# POWER.net
KiCad netlist of a schematic drawn in Altium Designer
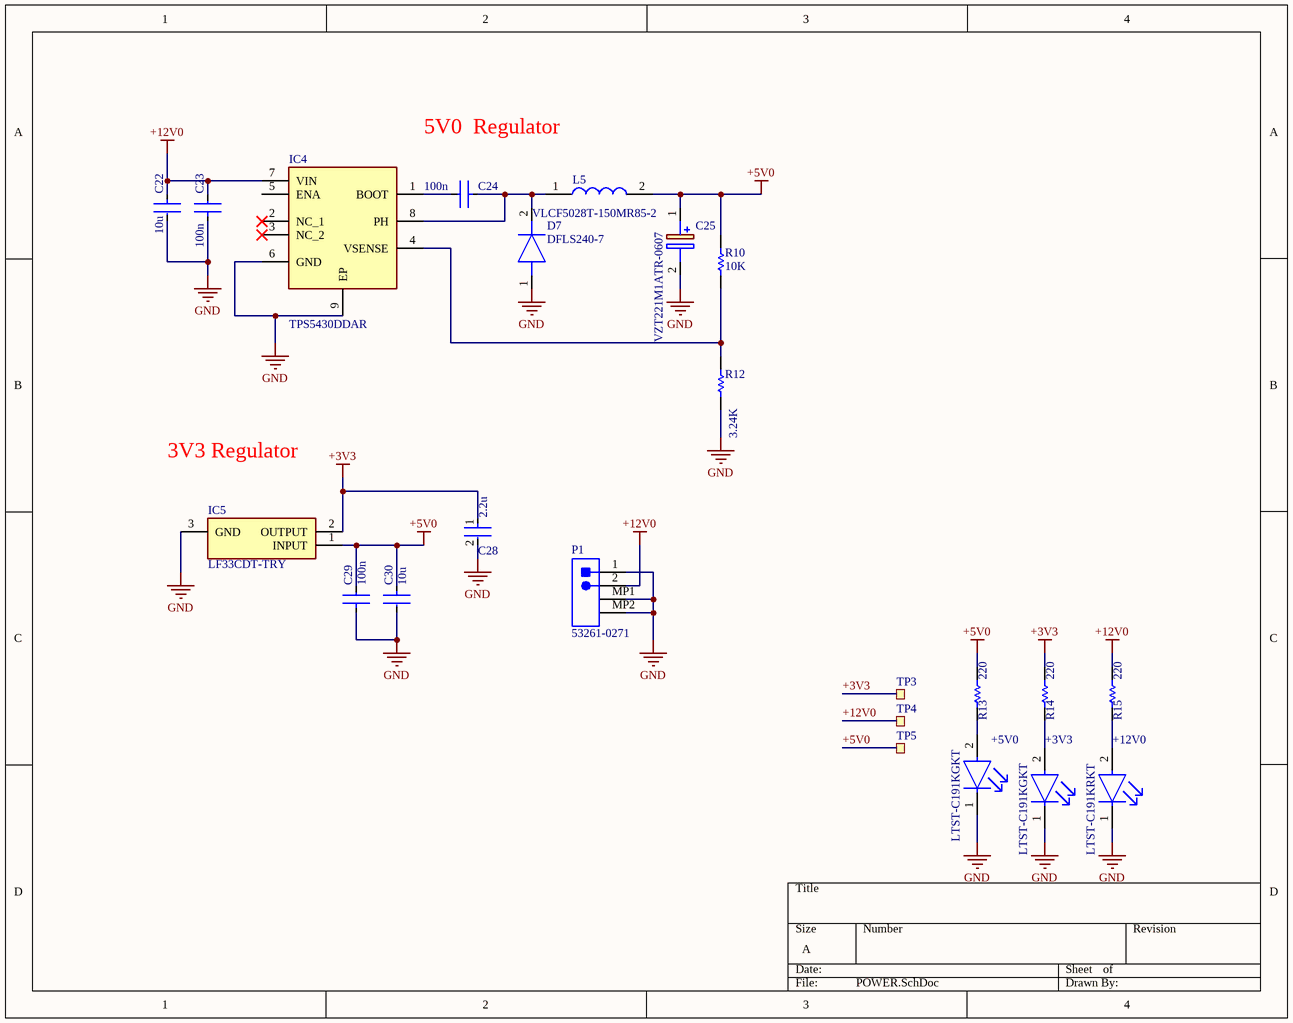
[diagram p0: POWER.SchDoc]

(export (version "E")
  (design (tool "Eeschema 10.0.6"))
  (components
    (comp (ref "+3V3")
      (value "LTST-C191KGKT")
      (footprint "FP-LTST-C191KGKT-MFG")
      (libsource (lib "Altium Content Vault") (part "8706943c75ba83719d021d2fdc84c58"))
    )
    (comp (ref "+5V0")
      (value "LTST-C191KGKT")
      (footprint "FP-LTST-C191KGKT-MFG")
      (libsource (lib "Altium Content Vault") (part "8706943c75ba83719d021d2fdc84c58"))
    )
    (comp (ref "+12V0")
      (value "LTST-C191KRKT")
      (footprint "FP-LTST-C191KRKT-MFG")
      (fields (field (name "VOLTAGE") "2V"))
      (libsource (lib "Altium Content Vault") (part "8706943c75ba83719d021d2fdc84c58"))
    )
    (comp (ref "C22")
      (value "10u")
      (footprint "FP-C1608-080-IPC_A")
      (description "CAP CER 10UF 25V X5R 0603")
      (fields (field (name "TOLERANCE") "20%") (field (name "Comment") "C1608X5R1E106M080AC"))
      (libsource (lib "") (part "11868f565c42a9108669ba33697ecf6_1"))
    )
    (comp (ref "C23")
      (value "100n")
      (footprint "FP-C1005-050-0_05-IPC_C")
      (description "Multilayer Ceramic Capacitors 100nF ±10% 50V X7R SMD 0402")
      (fields (field (name "VOLTAGE") "50V") (field (name "TOLERANCE") "10%"))
      (libsource (lib "Altium Content Vault") (part "b4654b650e69147ec39a6b967a45e02"))
    )
    (comp (ref "C24")
      (value "100n")
      (footprint "FP-C1005-050-0_05-IPC_C")
      (description "Multilayer Ceramic Capacitors 100nF ±10% 50V X7R SMD 0402")
      (fields (field (name "VOLTAGE") "50V") (field (name "TOLERANCE") "10%"))
      (libsource (lib "Altium Content Vault") (part "b4654b650e69147ec39a6b967a45e02"))
    )
    (comp (ref "C25")
      (value "VZT221M1ATR-0607")
      (footprint "SamacSys:CAPAE660X800N")
      (description "Capacitor Polarised")
      (fields (field (name "MOUSER PART NUMBER") "140-VZT221M1ATR-0607"))
      (libsource (lib "*") (part "VZT221M1ATR-0607"))
    )
    (comp (ref "C28")
      (value "C1005X5R1V225K050BC")
      (footprint "FP-C1005-050-0_15-IPC_A")
      (description "CAP CER 2.2UF 35V X5R 0402")
      (fields (field (name "CAPACITANCE") "2.2u") (field (name "TOLERANCE") "10%"))
      (libsource (lib "Altium Content Vault") (part "11868f565c42a9108669ba33697ecf6"))
    )
    (comp (ref "C29")
      (value "100n")
      (footprint "FP-C1005-050-0_05-IPC_C")
      (description "Multilayer Ceramic Capacitors 100nF ±10% 50V X7R SMD 0402")
      (fields (field (name "VOLTAGE") "50V") (field (name "TOLERANCE") "10%"))
      (libsource (lib "Altium Content Vault") (part "b4654b650e69147ec39a6b967a45e02"))
    )
    (comp (ref "C30")
      (value "10u")
      (footprint "FP-C1608-080-IPC_A")
      (description "CAP CER 10UF 25V X5R 0603")
      (fields (field (name "TOLERANCE") "20%") (field (name "Comment") "C1608X5R1E106M080AC"))
      (libsource (lib "") (part "11868f565c42a9108669ba33697ecf6_1"))
    )
    (comp (ref "D7")
      (value "DFLS240-7")
      (footprint "SamacSys:POWERDI123")
      (description "Diode")
      (fields (field (name "MOUSER PART NUMBER") "621-DFLS240-7"))
      (libsource (lib "*") (part "DFLS240-7"))
    )
    (comp (ref "IC4")
      (value "TPS5430DDAR")
      (footprint "SamacSys:SOIC127P600X170-9N")
      (description "Integrated Circuit")
      (fields (field (name "MOUSER PART NUMBER") "595-TPS5430DDAR"))
      (libsource (lib "SamacSys") (part "TPS5430DDAR"))
    )
    (comp (ref "IC5")
      (value "LF33CDT-TRY")
      (footprint "SamacSys:LD1117DT33")
      (description "Integrated Circuit")
      (fields (field (name "MOUSER PART NUMBER") "511-LF33CDT-TRY"))
      (libsource (lib "*") (part "LF33CDT-TRY"))
    )
    (comp (ref "L5")
      (value "VLCF5028T-150MR85-2")
      (footprint "SamacSys:VLCF5028")
      (description "Inductor")
      (fields (field (name "MOUSER PART NUMBER") "810-VLCF528T150MR852"))
      (libsource (lib "*") (part "VLCF5028T-150MR85-2"))
    )
    (comp (ref "P1")
      (value "53261-0271")
      (footprint "MOLX-53261-0271_V")
      (description "PicoBlade(TM) Header, Right Angle, -40 to 85 degC, 2-Pin SMD, RoHS, Tape and Reel")
      (fields (field (name "MANUFACTURER") "Molex"))
      (libsource (lib "Altium Content Vault") (part "CN-1P-2M-R2"))
    )
    (comp (ref "R10")
      (value "10K")
      (footprint "RESC1005X40X25LL05T10")
      (fields (field (name "PART NUMBER") "RC0402FR-0710KL") (field (name "MANUFACTURER") "Yageo / Phycomp"))
      (libsource (lib "Altium Content Vault") (part "RES"))
    )
    (comp (ref "R12")
      (value "3.24K")
      (footprint "RESC1005X40X25ML05T10")
      (fields (field (name "MANUFACTURER") "Yageo") (field (name "PART NUMBER") "RC0402FR-073K24L"))
      (libsource (lib "Altium Content Vault") (part "RES"))
    )
    (comp (ref "R13")
      (value "RC0402FR-13220RL")
      (footprint "RESC1005X40X25ML05T10")
      (fields (field (name "MANUFACTURER") "Yageo") (field (name "VLUE") "220"))
      (libsource (lib "Altium Content Vault") (part "RES"))
    )
    (comp (ref "R14")
      (value "RC0402FR-13220RL")
      (footprint "RESC1005X40X25ML05T10")
      (fields (field (name "MANUFACTURER") "Yageo") (field (name "VLUE") "220"))
      (libsource (lib "Altium Content Vault") (part "RES"))
    )
    (comp (ref "R15")
      (value "RC0402FR-13220RL")
      (footprint "RESC1005X40X25ML05T10")
      (fields (field (name "MANUFACTURER") "Yageo") (field (name "VLUE") "220"))
      (libsource (lib "Altium Content Vault") (part "RES"))
    )
    (comp (ref "TP3")
      (value "Ø1.5mm,SMD")
      (footprint "TP_SMD_Ø1.5mm")
      (description "1.5mm circular SMD testpad")
      (fields
        (field (name "PART NUMBER") "TP_SMD_Ø1.5MM")
        (field (name "MANUFACTURER") "Nordic Semiconductor")
      )
      (libsource (lib "ParsaLibrary") (part "TP_SMD_Ø1.5MM"))
    )
    (comp (ref "TP4")
      (value "Ø1.5mm,SMD")
      (footprint "TP_SMD_Ø1.5mm")
      (description "1.5mm circular SMD testpad")
      (fields
        (field (name "PART NUMBER") "TP_SMD_Ø1.5MM")
        (field (name "MANUFACTURER") "Nordic Semiconductor")
      )
      (libsource (lib "ParsaLibrary") (part "TP_SMD_Ø1.5MM"))
    )
    (comp (ref "TP5")
      (value "Ø1.5mm,SMD")
      (footprint "TP_SMD_Ø1.5mm")
      (description "1.5mm circular SMD testpad")
      (fields
        (field (name "PART NUMBER") "TP_SMD_Ø1.5MM")
        (field (name "MANUFACTURER") "Nordic Semiconductor")
      )
      (libsource (lib "ParsaLibrary") (part "TP_SMD_Ø1.5MM"))
    )
  )
  (nets
    (net (code "1") (name "+3V3") (class "Default")
      (node (ref "C28") (pin "1") (pinfunction "1_1") (pintype "passive"))
      (node (ref "IC5") (pin "2") (pinfunction "OUTPUT_2") (pintype "passive"))
      (node (ref "R14") (pin "2") (pinfunction "2_2") (pintype "passive"))
      (node (ref "TP3") (pin "1") (pinfunction "1_1") (pintype "passive"))
    )
    (net (code "2") (name "+5V0") (class "Default")
      (node (ref "C25") (pin "1") (pinfunction "+_1") (pintype "passive"))
      (node (ref "C29") (pin "2") (pinfunction "2_2") (pintype "passive"))
      (node (ref "C30") (pin "1") (pinfunction "1_1") (pintype "passive"))
      (node (ref "IC5") (pin "1") (pinfunction "INPUT_1") (pintype "passive"))
      (node (ref "L5") (pin "2") (pinfunction "2_2") (pintype "passive"))
      (node (ref "R10") (pin "1") (pinfunction "1_1") (pintype "passive"))
      (node (ref "R13") (pin "2") (pinfunction "2_2") (pintype "passive"))
      (node (ref "TP5") (pin "1") (pinfunction "1_1") (pintype "passive"))
    )
    (net (code "3") (name "+12V0") (class "Default")
      (node (ref "C22") (pin "1") (pinfunction "1_1") (pintype "passive"))
      (node (ref "C23") (pin "2") (pinfunction "2_2") (pintype "passive"))
      (node (ref "IC4") (pin "7") (pinfunction "VIN_7") (pintype "passive"))
      (node (ref "P1") (pin "2") (pinfunction "2_2") (pintype "passive"))
      (node (ref "R15") (pin "2") (pinfunction "2_2") (pintype "passive"))
      (node (ref "TP4") (pin "1") (pinfunction "1_1") (pintype "passive"))
    )
    (net (code "4") (name "GND") (class "Default")
      (node (ref "+12V0") (pin "1") (pinfunction "C_1") (pintype "passive"))
      (node (ref "+3V3") (pin "1") (pinfunction "C_1") (pintype "passive"))
      (node (ref "+5V0") (pin "1") (pinfunction "C_1") (pintype "passive"))
      (node (ref "C22") (pin "2") (pinfunction "2_2") (pintype "passive"))
      (node (ref "C23") (pin "1") (pinfunction "1_1") (pintype "passive"))
      (node (ref "C25") (pin "2") (pinfunction "-_2") (pintype "passive"))
      (node (ref "C28") (pin "2") (pinfunction "2_2") (pintype "passive"))
      (node (ref "C29") (pin "1") (pinfunction "1_1") (pintype "passive"))
      (node (ref "C30") (pin "2") (pinfunction "2_2") (pintype "passive"))
      (node (ref "D7") (pin "1") (pinfunction "A_1") (pintype "passive"))
      (node (ref "IC4") (pin "6") (pinfunction "GND_6") (pintype "passive"))
      (node (ref "IC4") (pin "9") (pinfunction "EP_9") (pintype "passive"))
      (node (ref "IC5") (pin "3") (pinfunction "GND_3") (pintype "passive"))
      (node (ref "P1") (pin "1") (pinfunction "1_1") (pintype "passive"))
      (node (ref "P1") (pin "MP1") (pinfunction "MP1_MP1") (pintype "passive"))
      (node (ref "P1") (pin "MP2") (pinfunction "MP2_MP2") (pintype "passive"))
      (node (ref "R12") (pin "1") (pinfunction "1_1") (pintype "passive"))
    )
    (net (code "5") (name "Net-(+3V3-A)") (class "Default")
      (node (ref "+3V3") (pin "2") (pinfunction "A_2") (pintype "passive"))
      (node (ref "R14") (pin "1") (pinfunction "1_1") (pintype "passive"))
    )
    (net (code "6") (name "Net-(+5V0-A)") (class "Default")
      (node (ref "+5V0") (pin "2") (pinfunction "A_2") (pintype "passive"))
      (node (ref "R13") (pin "1") (pinfunction "1_1") (pintype "passive"))
    )
    (net (code "7") (name "Net-(+12V0-A)") (class "Default")
      (node (ref "+12V0") (pin "2") (pinfunction "A_2") (pintype "passive"))
      (node (ref "R15") (pin "1") (pinfunction "1_1") (pintype "passive"))
    )
    (net (code "8") (name "Net-(D7-K)") (class "Default")
      (node (ref "C24") (pin "1") (pinfunction "1_1") (pintype "passive"))
      (node (ref "D7") (pin "2") (pinfunction "K_2") (pintype "passive"))
      (node (ref "IC4") (pin "8") (pinfunction "PH_8") (pintype "passive"))
      (node (ref "L5") (pin "1") (pinfunction "1_1") (pintype "passive"))
    )
    (net (code "9") (name "Net-(IC4-BOOT)") (class "Default")
      (node (ref "C24") (pin "2") (pinfunction "2_2") (pintype "passive"))
      (node (ref "IC4") (pin "1") (pinfunction "BOOT_1") (pintype "passive"))
    )
    (net (code "10") (name "Net-(IC4-VSENSE)") (class "Default")
      (node (ref "IC4") (pin "4") (pinfunction "VSENSE_4") (pintype "passive"))
      (node (ref "R10") (pin "2") (pinfunction "2_2") (pintype "passive"))
      (node (ref "R12") (pin "2") (pinfunction "2_2") (pintype "passive"))
    )
    (net (code "11") (name "unconnected-(IC4-ENA-Pad5)") (class "Default")
      (node (ref "IC4") (pin "5") (pinfunction "ENA_5") (pintype "passive"))
    )
    (net (code "12") (name "unconnected-(IC4-NC_1-Pad2)") (class "Default")
      (node (ref "IC4") (pin "2") (pinfunction "NC_1_2") (pintype "passive+no_connect"))
    )
    (net (code "13") (name "unconnected-(IC4-NC_2-Pad3)") (class "Default")
      (node (ref "IC4") (pin "3") (pinfunction "NC_2_3") (pintype "passive+no_connect"))
    )
  )
)
